# PWM_sheild_lilyGO.net
KiCad netlist of a schematic drawn in EAGLE
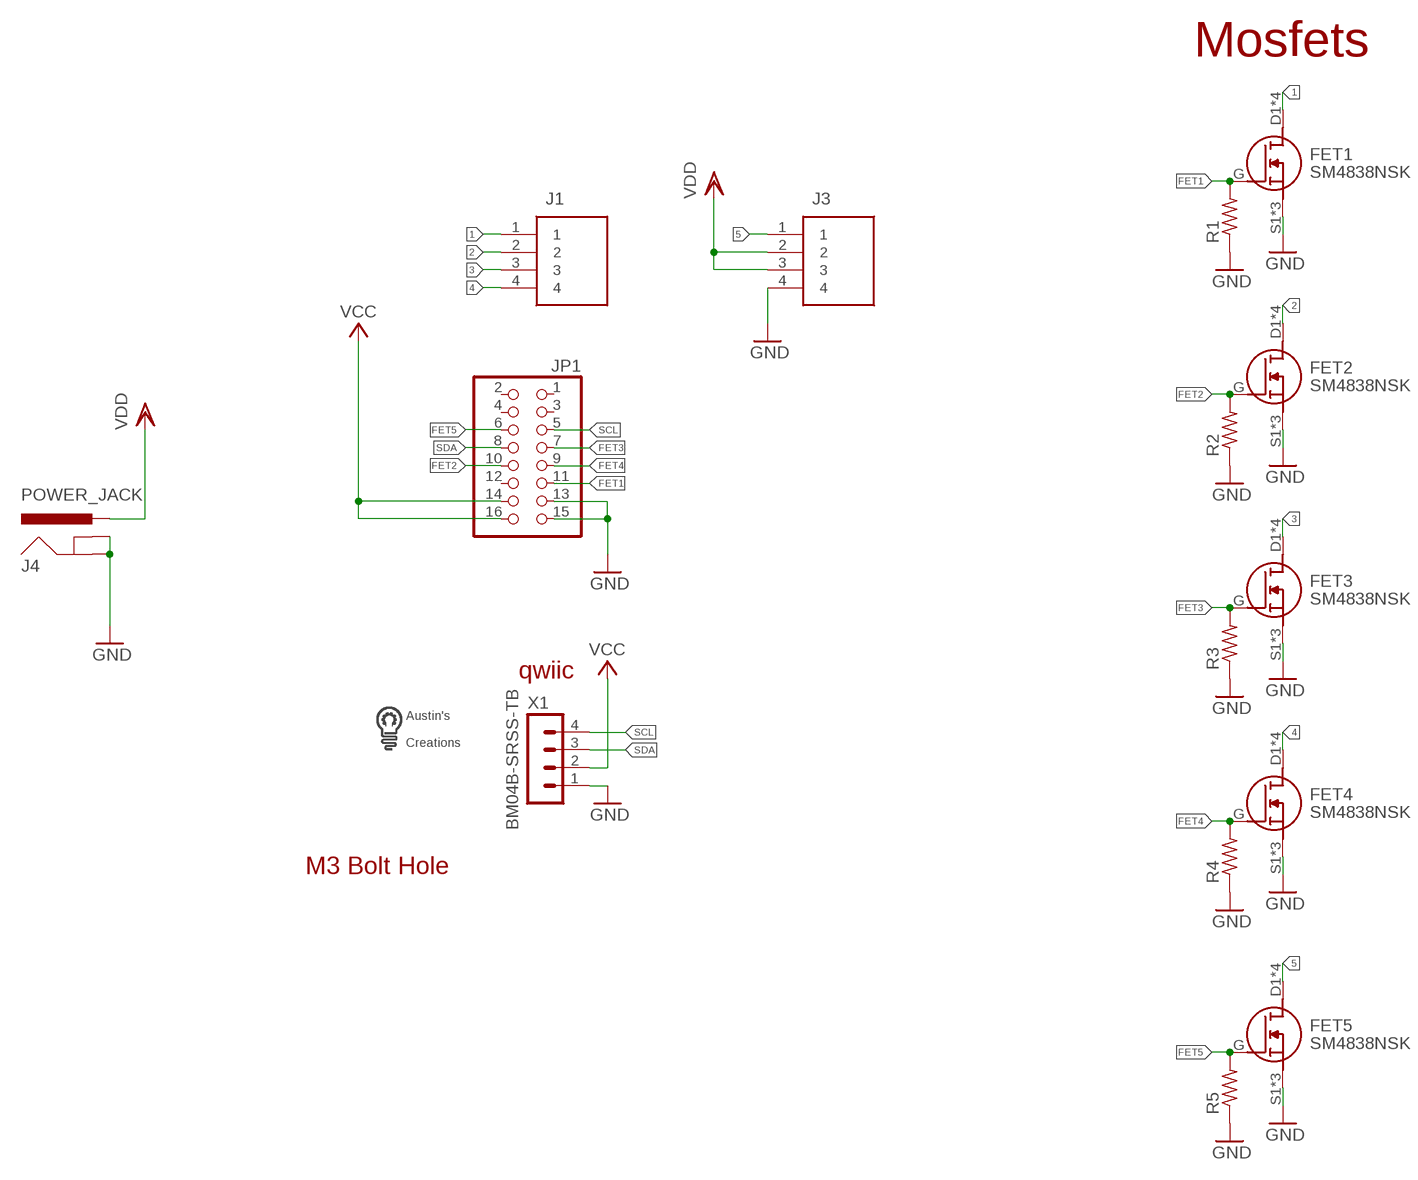
[diagram p0: schematic, sheet 1]

(export (version "E")
  (design (tool "Eeschema 10.0.6"))
  (components
    (comp (ref "FET1")
      (value "SM4838NSK")
      (footprint "eagle-import:SM4838NSK")
      (libsource (lib "eagle-import") (part "SM4838NSK"))
    )
    (comp (ref "FET2")
      (value "SM4838NSK")
      (footprint "eagle-import:SM4838NSK")
      (libsource (lib "eagle-import") (part "SM4838NSK"))
    )
    (comp (ref "FET3")
      (value "SM4838NSK")
      (footprint "eagle-import:SM4838NSK")
      (libsource (lib "eagle-import") (part "SM4838NSK"))
    )
    (comp (ref "FET4")
      (value "SM4838NSK")
      (footprint "eagle-import:SM4838NSK")
      (libsource (lib "eagle-import") (part "SM4838NSK"))
    )
    (comp (ref "FET5")
      (value "SM4838NSK")
      (footprint "eagle-import:SM4838NSK")
      (libsource (lib "eagle-import") (part "SM4838NSK"))
    )
    (comp (ref "J1")
      (value "SCREWTERMINAL-4P-5MM")
      (footprint "eagle-import:SCREWTERMINAL-4P-5MM")
      (fields
        (field (name "MANUFACTURER_PART_NUMBER") "TB001-500-04BE")
        (field (name "MOUSER_PART_NUMBER") "490-TB001-500-04BE")
      )
      (libsource (lib "eagle-import") (part "SCREWTERMINAL-4P-5MM"))
    )
    (comp (ref "J3")
      (value "SCREWTERMINAL-4P-5MM")
      (footprint "eagle-import:SCREWTERMINAL-4P-5MM")
      (fields
        (field (name "MANUFACTURER_PART_NUMBER") "TB001-500-04BE")
        (field (name "MOUSER_PART_NUMBER") "490-TB001-500-04BE")
      )
      (libsource (lib "eagle-import") (part "SCREWTERMINAL-4P-5MM"))
    )
    (comp (ref "J4")
      (value "POWER_JACK")
      (footprint "eagle-import:POWER_JACK_PTH")
      (libsource (lib "eagle-import") (part "POWER_JACK"))
    )
    (comp (ref "JP1")
      (value "PINHD-2X8")
      (footprint "eagle-import:2X08")
      (libsource (lib "eagle-import") (part "PINHD-2X8"))
    )
    (comp (ref "R1")
      (value "R-US_R0603")
      (footprint "eagle-import:R0603")
      (libsource (lib "eagle-import") (part "R-US_R0603"))
    )
    (comp (ref "R2")
      (value "R-US_R0603")
      (footprint "eagle-import:R0603")
      (libsource (lib "eagle-import") (part "R-US_R0603"))
    )
    (comp (ref "R3")
      (value "R-US_R0603")
      (footprint "eagle-import:R0603")
      (libsource (lib "eagle-import") (part "R-US_R0603"))
    )
    (comp (ref "R4")
      (value "R-US_R0603")
      (footprint "eagle-import:R0603")
      (libsource (lib "eagle-import") (part "R-US_R0603"))
    )
    (comp (ref "R5")
      (value "R-US_R0603")
      (footprint "eagle-import:R0603")
      (libsource (lib "eagle-import") (part "R-US_R0603"))
    )
    (comp (ref "U$1")
      (value "M3BOLTHOLE")
      (footprint "eagle-import:M3BOLTHOLE")
      (libsource (lib "eagle-import") (part "M3BOLTHOLE"))
    )
    (comp (ref "U$2")
      (value "LOGO")
      (footprint "eagle-import:LOGO")
      (libsource (lib "eagle-import") (part "LOGO"))
    )
    (comp (ref "X1")
      (value "BM04B-SRSS-TB")
      (footprint "eagle-import:BM04B-SRSS-TB")
      (libsource (lib "eagle-import") (part "BM04B-SRSS-TB"))
    )
  )
  (nets
    (net (code "1") (name "1") (class "Default")
      (node (ref "FET1") (pin "D1") (pinfunction "D_D1") (pintype "bidirectional"))
      (node (ref "FET1") (pin "D2") (pinfunction "D_D2") (pintype "bidirectional"))
      (node (ref "FET1") (pin "D3") (pinfunction "D_D3") (pintype "bidirectional"))
      (node (ref "FET1") (pin "D4") (pinfunction "D_D4") (pintype "bidirectional"))
      (node (ref "J1") (pin "1") (pinfunction "1_1") (pintype "bidirectional"))
    )
    (net (code "2") (name "2") (class "Default")
      (node (ref "FET2") (pin "D1") (pinfunction "D_D1") (pintype "bidirectional"))
      (node (ref "FET2") (pin "D2") (pinfunction "D_D2") (pintype "bidirectional"))
      (node (ref "FET2") (pin "D3") (pinfunction "D_D3") (pintype "bidirectional"))
      (node (ref "FET2") (pin "D4") (pinfunction "D_D4") (pintype "bidirectional"))
      (node (ref "J1") (pin "2") (pinfunction "2_2") (pintype "bidirectional"))
    )
    (net (code "3") (name "3") (class "Default")
      (node (ref "FET3") (pin "D1") (pinfunction "D_D1") (pintype "bidirectional"))
      (node (ref "FET3") (pin "D2") (pinfunction "D_D2") (pintype "bidirectional"))
      (node (ref "FET3") (pin "D3") (pinfunction "D_D3") (pintype "bidirectional"))
      (node (ref "FET3") (pin "D4") (pinfunction "D_D4") (pintype "bidirectional"))
      (node (ref "J1") (pin "3") (pinfunction "3_3") (pintype "bidirectional"))
    )
    (net (code "4") (name "4") (class "Default")
      (node (ref "FET4") (pin "D1") (pinfunction "D_D1") (pintype "bidirectional"))
      (node (ref "FET4") (pin "D2") (pinfunction "D_D2") (pintype "bidirectional"))
      (node (ref "FET4") (pin "D3") (pinfunction "D_D3") (pintype "bidirectional"))
      (node (ref "FET4") (pin "D4") (pinfunction "D_D4") (pintype "bidirectional"))
      (node (ref "J1") (pin "4") (pinfunction "4_4") (pintype "bidirectional"))
    )
    (net (code "5") (name "5") (class "Default")
      (node (ref "FET5") (pin "D1") (pinfunction "D_D1") (pintype "bidirectional"))
      (node (ref "FET5") (pin "D2") (pinfunction "D_D2") (pintype "bidirectional"))
      (node (ref "FET5") (pin "D3") (pinfunction "D_D3") (pintype "bidirectional"))
      (node (ref "FET5") (pin "D4") (pinfunction "D_D4") (pintype "bidirectional"))
      (node (ref "J3") (pin "1") (pinfunction "1_1") (pintype "bidirectional"))
    )
    (net (code "6") (name "FET1") (class "Default")
      (node (ref "FET1") (pin "G") (pinfunction "G_G") (pintype "bidirectional"))
      (node (ref "JP1") (pin "11") (pinfunction "11_11") (pintype "passive"))
      (node (ref "R1") (pin "2") (pinfunction "2_2") (pintype "passive"))
    )
    (net (code "7") (name "FET2") (class "Default")
      (node (ref "FET2") (pin "G") (pinfunction "G_G") (pintype "bidirectional"))
      (node (ref "JP1") (pin "10") (pinfunction "10_10") (pintype "passive"))
      (node (ref "R2") (pin "2") (pinfunction "2_2") (pintype "passive"))
    )
    (net (code "8") (name "FET3") (class "Default")
      (node (ref "FET3") (pin "G") (pinfunction "G_G") (pintype "bidirectional"))
      (node (ref "JP1") (pin "7") (pinfunction "7_7") (pintype "passive"))
      (node (ref "R3") (pin "2") (pinfunction "2_2") (pintype "passive"))
    )
    (net (code "9") (name "FET4") (class "Default")
      (node (ref "FET4") (pin "G") (pinfunction "G_G") (pintype "bidirectional"))
      (node (ref "JP1") (pin "9") (pinfunction "9_9") (pintype "passive"))
      (node (ref "R4") (pin "2") (pinfunction "2_2") (pintype "passive"))
    )
    (net (code "10") (name "FET5") (class "Default")
      (node (ref "FET5") (pin "G") (pinfunction "G_G") (pintype "bidirectional"))
      (node (ref "JP1") (pin "6") (pinfunction "6_6") (pintype "passive"))
      (node (ref "R5") (pin "2") (pinfunction "2_2") (pintype "passive"))
    )
    (net (code "11") (name "GND") (class "Default")
      (node (ref "FET1") (pin "S1") (pinfunction "S_S1") (pintype "bidirectional"))
      (node (ref "FET1") (pin "S2") (pinfunction "S_S2") (pintype "bidirectional"))
      (node (ref "FET1") (pin "S3") (pinfunction "S_S3") (pintype "bidirectional"))
      (node (ref "FET2") (pin "S1") (pinfunction "S_S1") (pintype "bidirectional"))
      (node (ref "FET2") (pin "S2") (pinfunction "S_S2") (pintype "bidirectional"))
      (node (ref "FET2") (pin "S3") (pinfunction "S_S3") (pintype "bidirectional"))
      (node (ref "FET3") (pin "S1") (pinfunction "S_S1") (pintype "bidirectional"))
      (node (ref "FET3") (pin "S2") (pinfunction "S_S2") (pintype "bidirectional"))
      (node (ref "FET3") (pin "S3") (pinfunction "S_S3") (pintype "bidirectional"))
      (node (ref "FET4") (pin "S1") (pinfunction "S_S1") (pintype "bidirectional"))
      (node (ref "FET4") (pin "S2") (pinfunction "S_S2") (pintype "bidirectional"))
      (node (ref "FET4") (pin "S3") (pinfunction "S_S3") (pintype "bidirectional"))
      (node (ref "FET5") (pin "S1") (pinfunction "S_S1") (pintype "bidirectional"))
      (node (ref "FET5") (pin "S2") (pinfunction "S_S2") (pintype "bidirectional"))
      (node (ref "FET5") (pin "S3") (pinfunction "S_S3") (pintype "bidirectional"))
      (node (ref "J3") (pin "4") (pinfunction "4_4") (pintype "bidirectional"))
      (node (ref "J4") (pin "GND") (pinfunction "GND_GND") (pintype "bidirectional"))
      (node (ref "J4") (pin "GNDBREAK") (pinfunction "GNDBREAK_GNDBREAK") (pintype "bidirectional"))
      (node (ref "JP1") (pin "13") (pinfunction "13_13") (pintype "passive"))
      (node (ref "JP1") (pin "15") (pinfunction "15_15") (pintype "passive"))
      (node (ref "R1") (pin "1") (pinfunction "1_1") (pintype "passive"))
      (node (ref "R2") (pin "1") (pinfunction "1_1") (pintype "passive"))
      (node (ref "R3") (pin "1") (pinfunction "1_1") (pintype "passive"))
      (node (ref "R4") (pin "1") (pinfunction "1_1") (pintype "passive"))
      (node (ref "R5") (pin "1") (pinfunction "1_1") (pintype "passive"))
      (node (ref "X1") (pin "1") (pinfunction "1_1") (pintype "passive"))
    )
    (net (code "12") (name "SCL") (class "Default")
      (node (ref "JP1") (pin "5") (pinfunction "5_5") (pintype "passive"))
      (node (ref "X1") (pin "4") (pinfunction "4_4") (pintype "passive"))
    )
    (net (code "13") (name "SDA") (class "Default")
      (node (ref "JP1") (pin "8") (pinfunction "8_8") (pintype "passive"))
      (node (ref "X1") (pin "3") (pinfunction "3_3") (pintype "passive"))
    )
    (net (code "14") (name "VCC") (class "Default")
      (node (ref "JP1") (pin "14") (pinfunction "14_14") (pintype "passive"))
      (node (ref "JP1") (pin "16") (pinfunction "16_16") (pintype "passive"))
      (node (ref "X1") (pin "2") (pinfunction "2_2") (pintype "passive"))
    )
    (net (code "15") (name "VDD") (class "Default")
      (node (ref "J3") (pin "2") (pinfunction "2_2") (pintype "bidirectional"))
      (node (ref "J3") (pin "3") (pinfunction "3_3") (pintype "bidirectional"))
      (node (ref "J4") (pin "PWR") (pinfunction "PWR_PWR") (pintype "bidirectional"))
    )
    (net (code "16") (name "unconnected-(JP1-Pad1)") (class "Default")
      (node (ref "JP1") (pin "1") (pinfunction "1_1") (pintype "passive"))
    )
    (net (code "17") (name "unconnected-(JP1-Pad2)") (class "Default")
      (node (ref "JP1") (pin "2") (pinfunction "2_2") (pintype "passive"))
    )
    (net (code "18") (name "unconnected-(JP1-Pad3)") (class "Default")
      (node (ref "JP1") (pin "3") (pinfunction "3_3") (pintype "passive"))
    )
    (net (code "19") (name "unconnected-(JP1-Pad4)") (class "Default")
      (node (ref "JP1") (pin "4") (pinfunction "4_4") (pintype "passive"))
    )
    (net (code "20") (name "unconnected-(JP1-Pad12)") (class "Default")
      (node (ref "JP1") (pin "12") (pinfunction "12_12") (pintype "passive"))
    )
  )
)
